# Power.net
KiCad netlist of a schematic drawn in Altium Designer
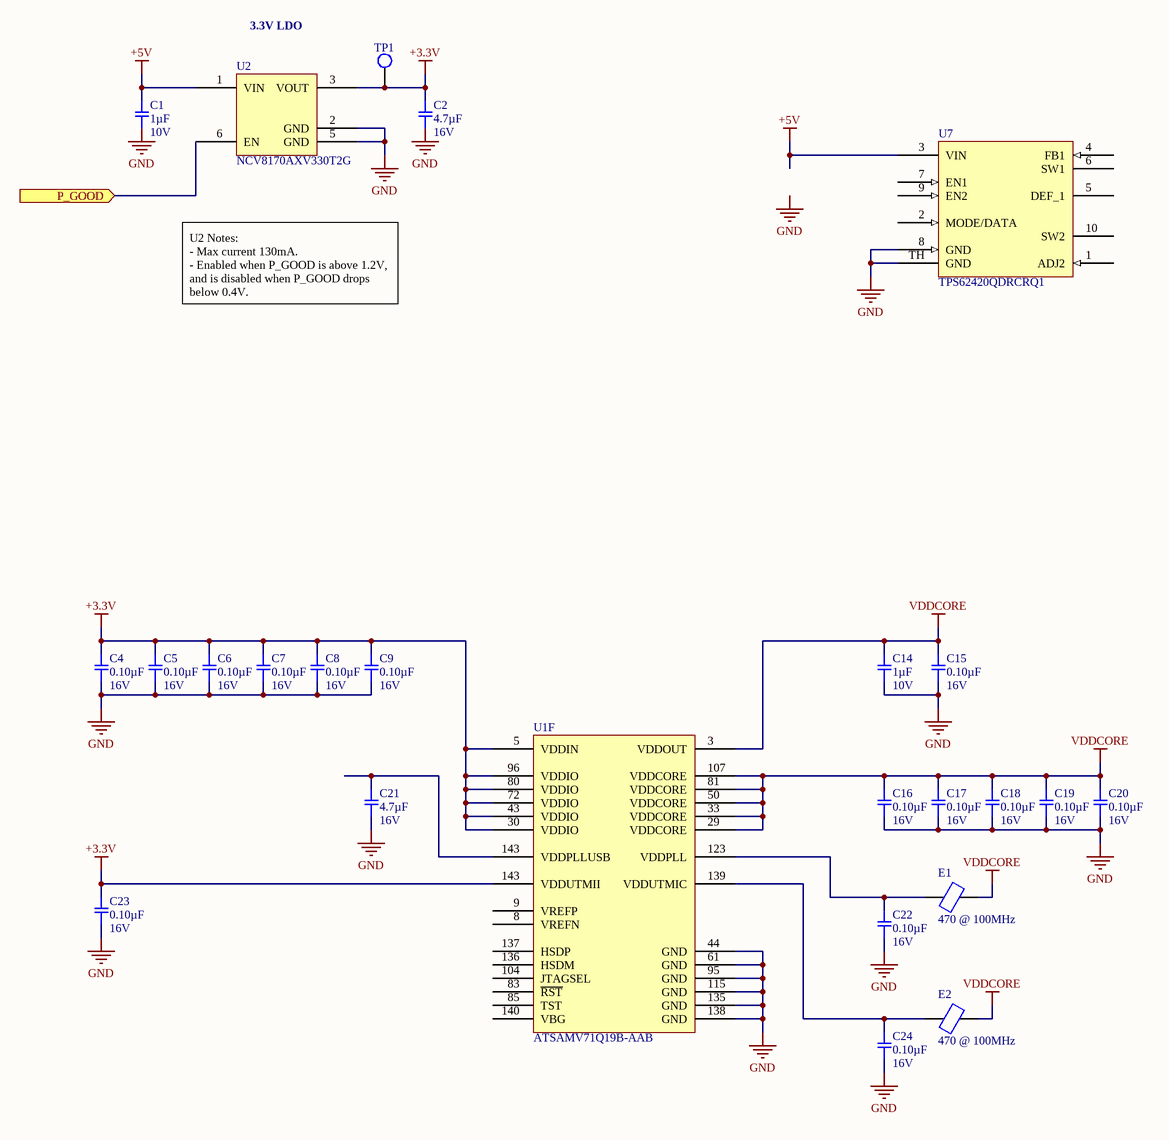
[diagram p0: Power.SchDoc]

(export (version "E")
  (design (tool "Eeschema 10.0.6"))
  (components
    (comp (ref "C1")
      (value "1µF")
      (footprint "SMD-0402C")
      (description "CAP CER 1UF 10V X7S 0402")
      (fields
        (field (name "DIGI-KEY PART NUMBER") "490-13409-1-ND")
        (field (name "PART NUMBER") "GCM155C71A105KE38D")
        (field (name "VOLTAGE") "10V")
      )
      (libsource (lib "capacitor_murata_0402") (part "GCM155C71A105KE38D"))
    )
    (comp (ref "C2")
      (value "4.7µF")
      (footprint "SMD-0805C")
      (description "CAP CER 4.7UF 16V X7R 0805")
      (fields
        (field (name "DIGI-KEY PART NUMBER") "490-10557-1-ND")
        (field (name "PART NUMBER") "GCJ21BR71C475KA01L")
        (field (name "VOLTAGE") "16V")
      )
      (libsource (lib "capacitor_murata_0805") (part "GCJ21BR71C475KA01L"))
    )
    (comp (ref "C4")
      (value "0.10µF")
      (footprint "SMD-0402C")
      (description "CAP CER 0.1UF 16V X7R 0402")
      (fields
        (field (name "DIGI-KEY PART NUMBER") "490-4759-1-ND")
        (field (name "PART NUMBER") "GCM155R71C104KA55D")
        (field (name "VOLTAGE") "16V")
      )
      (libsource (lib "capacitor_murata_0402") (part "GCM155R71C104KA55D"))
    )
    (comp (ref "C5")
      (value "0.10µF")
      (footprint "SMD-0402C")
      (description "CAP CER 0.1UF 16V X7R 0402")
      (fields
        (field (name "DIGI-KEY PART NUMBER") "490-4759-1-ND")
        (field (name "PART NUMBER") "GCM155R71C104KA55D")
        (field (name "VOLTAGE") "16V")
      )
      (libsource (lib "capacitor_murata_0402") (part "GCM155R71C104KA55D"))
    )
    (comp (ref "C6")
      (value "0.10µF")
      (footprint "SMD-0402C")
      (description "CAP CER 0.1UF 16V X7R 0402")
      (fields
        (field (name "DIGI-KEY PART NUMBER") "490-4759-1-ND")
        (field (name "PART NUMBER") "GCM155R71C104KA55D")
        (field (name "VOLTAGE") "16V")
      )
      (libsource (lib "capacitor_murata_0402") (part "GCM155R71C104KA55D"))
    )
    (comp (ref "C7")
      (value "0.10µF")
      (footprint "SMD-0402C")
      (description "CAP CER 0.1UF 16V X7R 0402")
      (fields
        (field (name "DIGI-KEY PART NUMBER") "490-4759-1-ND")
        (field (name "PART NUMBER") "GCM155R71C104KA55D")
        (field (name "VOLTAGE") "16V")
      )
      (libsource (lib "capacitor_murata_0402") (part "GCM155R71C104KA55D"))
    )
    (comp (ref "C8")
      (value "0.10µF")
      (footprint "SMD-0402C")
      (description "CAP CER 0.1UF 16V X7R 0402")
      (fields
        (field (name "DIGI-KEY PART NUMBER") "490-4759-1-ND")
        (field (name "PART NUMBER") "GCM155R71C104KA55D")
        (field (name "VOLTAGE") "16V")
      )
      (libsource (lib "capacitor_murata_0402") (part "GCM155R71C104KA55D"))
    )
    (comp (ref "C9")
      (value "0.10µF")
      (footprint "SMD-0402C")
      (description "CAP CER 0.1UF 16V X7R 0402")
      (fields
        (field (name "DIGI-KEY PART NUMBER") "490-4759-1-ND")
        (field (name "PART NUMBER") "GCM155R71C104KA55D")
        (field (name "VOLTAGE") "16V")
      )
      (libsource (lib "capacitor_murata_0402") (part "GCM155R71C104KA55D"))
    )
    (comp (ref "C14")
      (value "1µF")
      (footprint "SMD-0402C")
      (description "CAP CER 1UF 10V X7S 0402")
      (fields
        (field (name "DIGI-KEY PART NUMBER") "490-13409-1-ND")
        (field (name "PART NUMBER") "GCM155C71A105KE38D")
        (field (name "VOLTAGE") "10V")
      )
      (libsource (lib "capacitor_murata_0402") (part "GCM155C71A105KE38D"))
    )
    (comp (ref "C15")
      (value "0.10µF")
      (footprint "SMD-0402C")
      (description "CAP CER 0.1UF 16V X7R 0402")
      (fields
        (field (name "DIGI-KEY PART NUMBER") "490-4759-1-ND")
        (field (name "PART NUMBER") "GCM155R71C104KA55D")
        (field (name "VOLTAGE") "16V")
      )
      (libsource (lib "capacitor_murata_0402") (part "GCM155R71C104KA55D"))
    )
    (comp (ref "C16")
      (value "0.10µF")
      (footprint "SMD-0402C")
      (description "CAP CER 0.1UF 16V X7R 0402")
      (fields
        (field (name "DIGI-KEY PART NUMBER") "490-4759-1-ND")
        (field (name "PART NUMBER") "GCM155R71C104KA55D")
        (field (name "VOLTAGE") "16V")
      )
      (libsource (lib "capacitor_murata_0402") (part "GCM155R71C104KA55D"))
    )
    (comp (ref "C17")
      (value "0.10µF")
      (footprint "SMD-0402C")
      (description "CAP CER 0.1UF 16V X7R 0402")
      (fields
        (field (name "DIGI-KEY PART NUMBER") "490-4759-1-ND")
        (field (name "PART NUMBER") "GCM155R71C104KA55D")
        (field (name "VOLTAGE") "16V")
      )
      (libsource (lib "capacitor_murata_0402") (part "GCM155R71C104KA55D"))
    )
    (comp (ref "C18")
      (value "0.10µF")
      (footprint "SMD-0402C")
      (description "CAP CER 0.1UF 16V X7R 0402")
      (fields
        (field (name "DIGI-KEY PART NUMBER") "490-4759-1-ND")
        (field (name "PART NUMBER") "GCM155R71C104KA55D")
        (field (name "VOLTAGE") "16V")
      )
      (libsource (lib "capacitor_murata_0402") (part "GCM155R71C104KA55D"))
    )
    (comp (ref "C19")
      (value "0.10µF")
      (footprint "SMD-0402C")
      (description "CAP CER 0.1UF 16V X7R 0402")
      (fields
        (field (name "DIGI-KEY PART NUMBER") "490-4759-1-ND")
        (field (name "PART NUMBER") "GCM155R71C104KA55D")
        (field (name "VOLTAGE") "16V")
      )
      (libsource (lib "capacitor_murata_0402") (part "GCM155R71C104KA55D"))
    )
    (comp (ref "C20")
      (value "0.10µF")
      (footprint "SMD-0402C")
      (description "CAP CER 0.1UF 16V X7R 0402")
      (fields
        (field (name "DIGI-KEY PART NUMBER") "490-4759-1-ND")
        (field (name "PART NUMBER") "GCM155R71C104KA55D")
        (field (name "VOLTAGE") "16V")
      )
      (libsource (lib "capacitor_murata_0402") (part "GCM155R71C104KA55D"))
    )
    (comp (ref "C21")
      (value "4.7µF")
      (footprint "SMD-0805C")
      (description "CAP CER 4.7UF 16V X7R 0805")
      (fields
        (field (name "DIGI-KEY PART NUMBER") "490-10557-1-ND")
        (field (name "PART NUMBER") "GCJ21BR71C475KA01L")
        (field (name "VOLTAGE") "16V")
      )
      (libsource (lib "capacitor_murata_0805") (part "GCJ21BR71C475KA01L"))
    )
    (comp (ref "C22")
      (value "0.10µF")
      (footprint "SMD-0402C")
      (description "CAP CER 0.1UF 16V X7R 0402")
      (fields
        (field (name "DIGI-KEY PART NUMBER") "490-4759-1-ND")
        (field (name "PART NUMBER") "GCM155R71C104KA55D")
        (field (name "VOLTAGE") "16V")
      )
      (libsource (lib "capacitor_murata_0402") (part "GCM155R71C104KA55D"))
    )
    (comp (ref "C23")
      (value "0.10µF")
      (footprint "SMD-0402C")
      (description "CAP CER 0.1UF 16V X7R 0402")
      (fields
        (field (name "DIGI-KEY PART NUMBER") "490-4759-1-ND")
        (field (name "PART NUMBER") "GCM155R71C104KA55D")
        (field (name "VOLTAGE") "16V")
      )
      (libsource (lib "capacitor_murata_0402") (part "GCM155R71C104KA55D"))
    )
    (comp (ref "C24")
      (value "0.10µF")
      (footprint "SMD-0402C")
      (description "CAP CER 0.1UF 16V X7R 0402")
      (fields
        (field (name "DIGI-KEY PART NUMBER") "490-4759-1-ND")
        (field (name "PART NUMBER") "GCM155R71C104KA55D")
        (field (name "VOLTAGE") "16V")
      )
      (libsource (lib "capacitor_murata_0402") (part "GCM155R71C104KA55D"))
    )
    (comp (ref "E1")
      (value "470 @ 100MHz")
      (fields (field (name "Comment") "MPZ1608S471ATD25"))
      (libsource (lib "ModularPayload") (part "MPZ1608S471ATD25"))
    )
    (comp (ref "E2")
      (value "470 @ 100MHz")
      (fields (field (name "Comment") "MPZ1608S471ATD25"))
      (libsource (lib "ModularPayload") (part "MPZ1608S471ATD25"))
    )
    (comp (ref "TP1") (value "TP") (footprint "TP_SMD_40") (libsource (lib "TP") (part "TP")))
    (comp (ref "U1")
      (value "ATSAMV71Q19B-AAB")
      (footprint "TSQFP50P2200X2200X160-144N")
      (libsource (lib "ModularPayload") (part "ATSAMV71Q19B-AAB"))
    )
    (comp (ref "U2")
      (value "NCV8170AXV330T2G")
      (footprint "SOTFL50P160X60-6N")
      (libsource (lib "ModularPayload") (part "NCV8170AXV330T2G"))
    )
    (comp (ref "U7") (value "TPS62420QDRCRQ1") (libsource (lib "ModularPayload") (part "TPS62420QDRCRQ1")))
  )
  (nets
    (net (code "1") (name "+3.3V") (class "Default")
      (node (ref "C2") (pin "2") (pinfunction "2_2") (pintype "passive"))
      (node (ref "C23") (pin "2") (pinfunction "2_2") (pintype "passive"))
      (node (ref "C4") (pin "2") (pinfunction "2_2") (pintype "passive"))
      (node (ref "C5") (pin "2") (pinfunction "2_2") (pintype "passive"))
      (node (ref "C6") (pin "2") (pinfunction "2_2") (pintype "passive"))
      (node (ref "C7") (pin "2") (pinfunction "2_2") (pintype "passive"))
      (node (ref "C8") (pin "2") (pinfunction "2_2") (pintype "passive"))
      (node (ref "C9") (pin "2") (pinfunction "2_2") (pintype "passive"))
      (node (ref "TP1") (pin "1") (pintype "passive"))
      (node (ref "U1") (pin "143") (pinfunction "VDDUTMII_143") (pintype "passive"))
      (node (ref "U1") (pin "30") (pinfunction "VDDIO_30") (pintype "passive"))
      (node (ref "U1") (pin "43") (pinfunction "VDDIO_43") (pintype "passive"))
      (node (ref "U1") (pin "5") (pinfunction "VDDIN_5") (pintype "passive"))
      (node (ref "U1") (pin "72") (pinfunction "VDDIO_72") (pintype "passive"))
      (node (ref "U1") (pin "80") (pinfunction "VDDIO_80") (pintype "passive"))
      (node (ref "U1") (pin "96") (pinfunction "VDDIO_96") (pintype "passive"))
      (node (ref "U2") (pin "3") (pinfunction "VOUT_3") (pintype "passive"))
    )
    (net (code "2") (name "+5V") (class "Default")
      (node (ref "C1") (pin "2") (pinfunction "2_2") (pintype "passive"))
      (node (ref "U2") (pin "1") (pinfunction "VIN_1") (pintype "passive"))
      (node (ref "U7") (pin "3") (pinfunction "VIN_3") (pintype "power_in"))
    )
    (net (code "3") (name "/P_GOOD") (class "Default")
      (node (ref "U2") (pin "6") (pinfunction "EN_6") (pintype "passive"))
    )
    (net (code "4") (name "GND") (class "Default")
      (node (ref "C1") (pin "1") (pinfunction "1_1") (pintype "passive"))
      (node (ref "C14") (pin "1") (pinfunction "1_1") (pintype "passive"))
      (node (ref "C15") (pin "1") (pinfunction "1_1") (pintype "passive"))
      (node (ref "C16") (pin "1") (pinfunction "1_1") (pintype "passive"))
      (node (ref "C17") (pin "1") (pinfunction "1_1") (pintype "passive"))
      (node (ref "C18") (pin "1") (pinfunction "1_1") (pintype "passive"))
      (node (ref "C19") (pin "1") (pinfunction "1_1") (pintype "passive"))
      (node (ref "C2") (pin "1") (pinfunction "1_1") (pintype "passive"))
      (node (ref "C20") (pin "1") (pinfunction "1_1") (pintype "passive"))
      (node (ref "C21") (pin "1") (pinfunction "1_1") (pintype "passive"))
      (node (ref "C22") (pin "1") (pinfunction "1_1") (pintype "passive"))
      (node (ref "C23") (pin "1") (pinfunction "1_1") (pintype "passive"))
      (node (ref "C24") (pin "1") (pinfunction "1_1") (pintype "passive"))
      (node (ref "C4") (pin "1") (pinfunction "1_1") (pintype "passive"))
      (node (ref "C5") (pin "1") (pinfunction "1_1") (pintype "passive"))
      (node (ref "C6") (pin "1") (pinfunction "1_1") (pintype "passive"))
      (node (ref "C7") (pin "1") (pinfunction "1_1") (pintype "passive"))
      (node (ref "C8") (pin "1") (pinfunction "1_1") (pintype "passive"))
      (node (ref "C9") (pin "1") (pinfunction "1_1") (pintype "passive"))
      (node (ref "U1") (pin "115") (pinfunction "GND_115") (pintype "passive"))
      (node (ref "U1") (pin "135") (pinfunction "GND_135") (pintype "passive"))
      (node (ref "U1") (pin "138") (pinfunction "GND_138") (pintype "passive"))
      (node (ref "U1") (pin "44") (pinfunction "GND_44") (pintype "passive"))
      (node (ref "U1") (pin "61") (pinfunction "GND_61") (pintype "passive"))
      (node (ref "U1") (pin "95") (pinfunction "GND_95") (pintype "passive"))
      (node (ref "U2") (pin "2") (pinfunction "GND_2") (pintype "passive"))
      (node (ref "U2") (pin "5") (pinfunction "GND_5") (pintype "passive"))
      (node (ref "U7") (pin "8") (pinfunction "GND_8") (pintype "input"))
      (node (ref "U7") (pin "TH") (pinfunction "GND_TH") (pintype "passive"))
    )
    (net (code "5") (name "Net-(U1F-VDDPLL)") (class "Default")
      (node (ref "C22") (pin "2") (pinfunction "2_2") (pintype "passive"))
      (node (ref "E1") (pin "1") (pinfunction "1_1") (pintype "passive"))
      (node (ref "U1") (pin "123") (pinfunction "VDDPLL_123") (pintype "passive"))
    )
    (net (code "6") (name "Net-(U1F-VDDPLLUSB)") (class "Default")
      (node (ref "C21") (pin "2") (pinfunction "2_2") (pintype "passive"))
      (node (ref "U1") (pin "143") (pinfunction "VDDPLLUSB_143") (pintype "passive"))
    )
    (net (code "7") (name "Net-(U1F-VDDUTMIC)") (class "Default")
      (node (ref "C24") (pin "2") (pinfunction "2_2") (pintype "passive"))
      (node (ref "E2") (pin "1") (pinfunction "1_1") (pintype "passive"))
      (node (ref "U1") (pin "139") (pinfunction "VDDUTMIC_139") (pintype "passive"))
    )
    (net (code "8") (name "VDDCORE") (class "Default")
      (node (ref "C14") (pin "2") (pinfunction "2_2") (pintype "passive"))
      (node (ref "C15") (pin "2") (pinfunction "2_2") (pintype "passive"))
      (node (ref "C16") (pin "2") (pinfunction "2_2") (pintype "passive"))
      (node (ref "C17") (pin "2") (pinfunction "2_2") (pintype "passive"))
      (node (ref "C18") (pin "2") (pinfunction "2_2") (pintype "passive"))
      (node (ref "C19") (pin "2") (pinfunction "2_2") (pintype "passive"))
      (node (ref "C20") (pin "2") (pinfunction "2_2") (pintype "passive"))
      (node (ref "E1") (pin "2") (pinfunction "2_2") (pintype "passive"))
      (node (ref "E2") (pin "2") (pinfunction "2_2") (pintype "passive"))
      (node (ref "U1") (pin "107") (pinfunction "VDDCORE_107") (pintype "passive"))
      (node (ref "U1") (pin "29") (pinfunction "VDDCORE_29") (pintype "passive"))
      (node (ref "U1") (pin "3") (pinfunction "VDDOUT_3") (pintype "passive"))
      (node (ref "U1") (pin "33") (pinfunction "VDDCORE_33") (pintype "passive"))
      (node (ref "U1") (pin "50") (pinfunction "VDDCORE_50") (pintype "passive"))
      (node (ref "U1") (pin "81") (pinfunction "VDDCORE_81") (pintype "passive"))
    )
    (net (code "9") (name "unconnected-(U1F-HSDM-Pad136)") (class "Default")
      (node (ref "U1") (pin "136") (pinfunction "HSDM_136") (pintype "passive"))
    )
    (net (code "10") (name "unconnected-(U1F-HSDP-Pad137)") (class "Default")
      (node (ref "U1") (pin "137") (pinfunction "HSDP_137") (pintype "passive"))
    )
    (net (code "11") (name "unconnected-(U1F-JTAGSEL-Pad104)") (class "Default")
      (node (ref "U1") (pin "104") (pinfunction "JTAGSEL_104") (pintype "passive"))
    )
    (net (code "12") (name "unconnected-(U1F-TST-Pad85)") (class "Default")
      (node (ref "U1") (pin "85") (pinfunction "TST_85") (pintype "passive"))
    )
    (net (code "13") (name "unconnected-(U1F-VBG-Pad140)") (class "Default")
      (node (ref "U1") (pin "140") (pinfunction "VBG_140") (pintype "passive"))
    )
    (net (code "14") (name "unconnected-(U1F-VREFN-Pad8)") (class "Default")
      (node (ref "U1") (pin "8") (pinfunction "VREFN_8") (pintype "passive"))
    )
    (net (code "15") (name "unconnected-(U1F-VREFP-Pad9)") (class "Default")
      (node (ref "U1") (pin "9") (pinfunction "VREFP_9") (pintype "passive"))
    )
    (net (code "16") (name "unconnected-(U1F-~{RST}-Pad83)") (class "Default")
      (node (ref "U1") (pin "83") (pinfunction "~{RST}_83") (pintype "passive"))
    )
    (net (code "17") (name "unconnected-(U7-ADJ2-Pad1)") (class "Default")
      (node (ref "U7") (pin "1") (pinfunction "ADJ2_1") (pintype "input"))
    )
    (net (code "18") (name "unconnected-(U7-DEF_1-Pad5)") (class "Default")
      (node (ref "U7") (pin "5") (pinfunction "DEF_1_5") (pintype "passive"))
    )
    (net (code "19") (name "unconnected-(U7-EN1-Pad7)") (class "Default")
      (node (ref "U7") (pin "7") (pinfunction "EN1_7") (pintype "input"))
    )
    (net (code "20") (name "unconnected-(U7-EN2-Pad9)") (class "Default")
      (node (ref "U7") (pin "9") (pinfunction "EN2_9") (pintype "input"))
    )
    (net (code "21") (name "unconnected-(U7-FB1-Pad4)") (class "Default")
      (node (ref "U7") (pin "4") (pinfunction "FB1_4") (pintype "input"))
    )
    (net (code "22") (name "unconnected-(U7-MODE{slash}DATA-Pad2)") (class "Default")
      (node (ref "U7") (pin "2") (pinfunction "MODE/DATA_2") (pintype "input"))
    )
    (net (code "23") (name "unconnected-(U7-SW1-Pad6)") (class "Default")
      (node (ref "U7") (pin "6") (pinfunction "SW1_6") (pintype "passive"))
    )
    (net (code "24") (name "unconnected-(U7-SW2-Pad10)") (class "Default")
      (node (ref "U7") (pin "10") (pinfunction "SW2_10") (pintype "passive"))
    )
  )
)
